# geigera-mullera.net
KiCad netlist of a schematic drawn in EAGLE
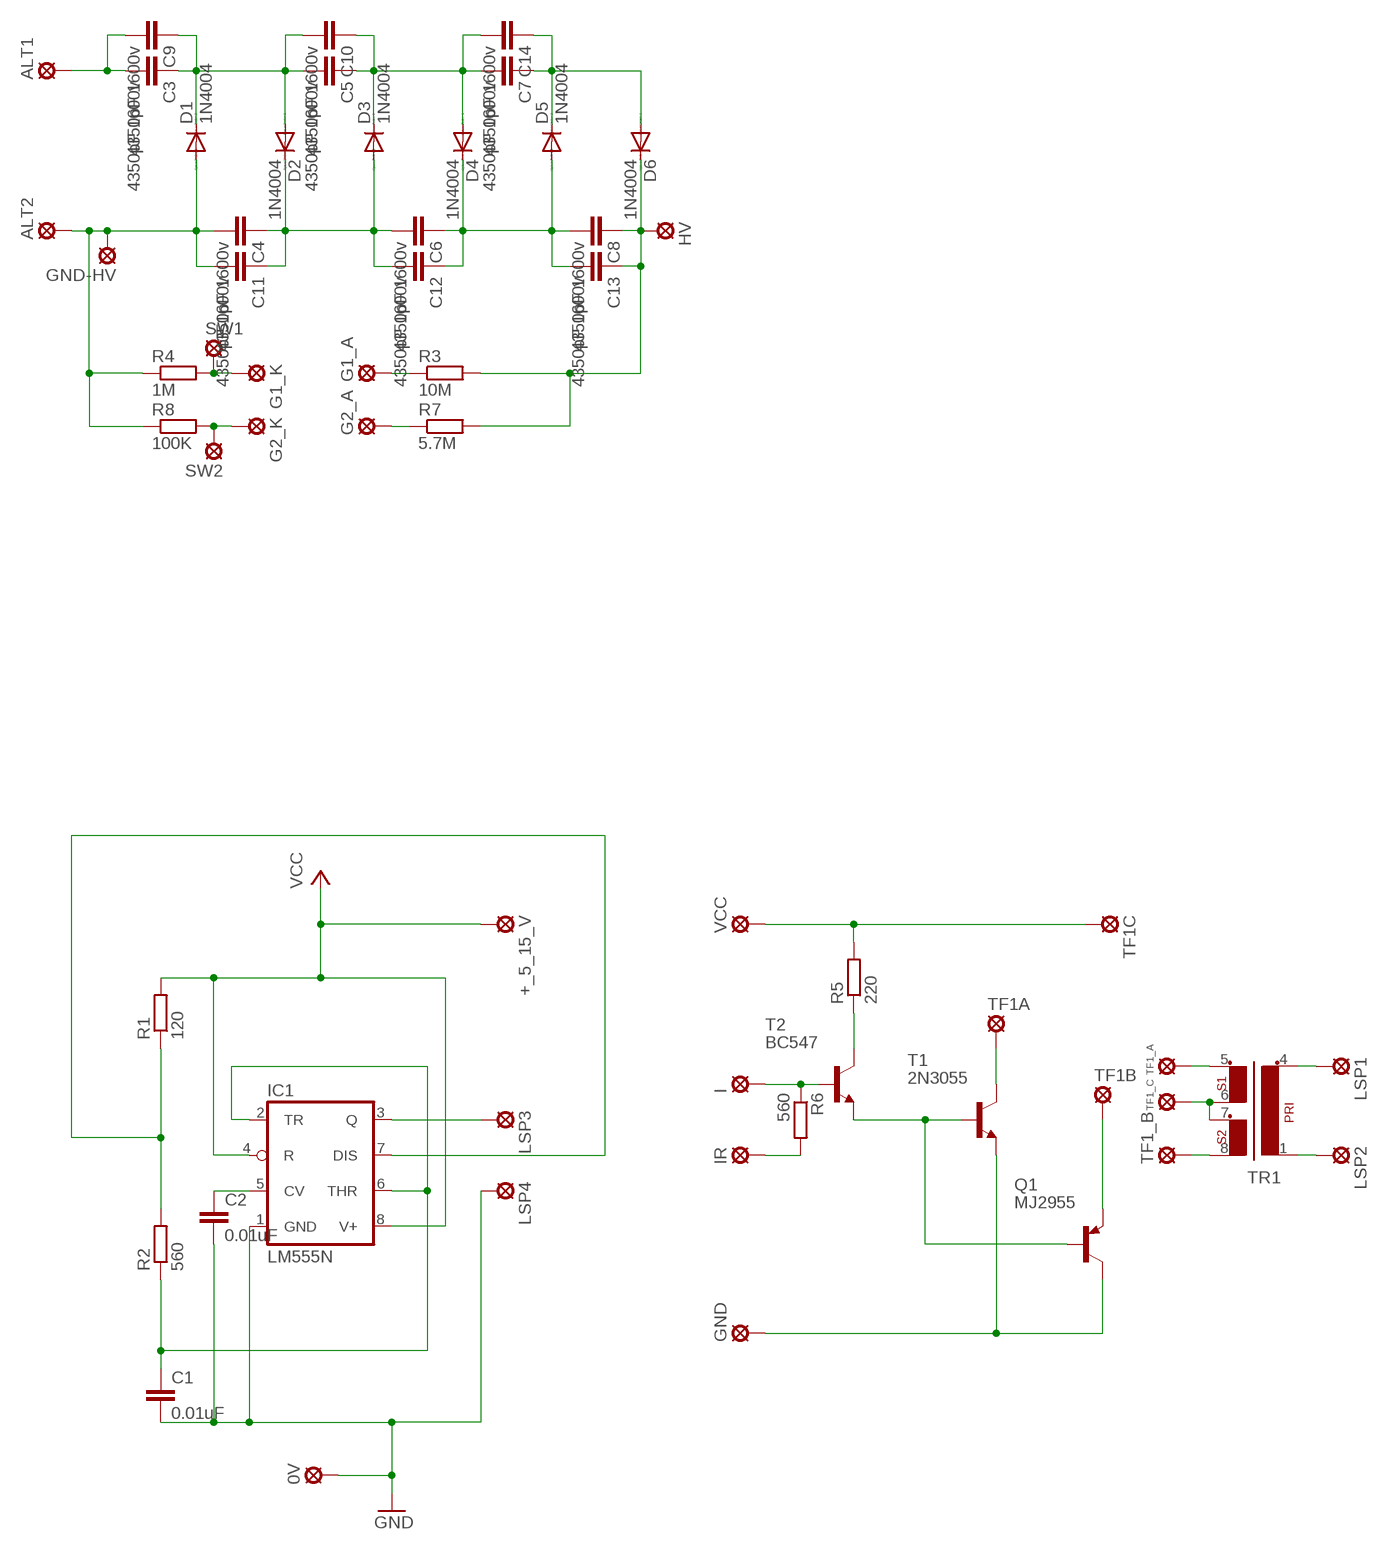
[diagram p0: schematic, sheet 1]

(export (version "E")
  (design (tool "Eeschema 10.0.6"))
  (components
    (comp (ref "+_5_15_V")
      (value "LSP10")
      (footprint "eagle-import:LSP10")
      (libsource (lib "eagle-import") (part "LSP10"))
    )
    (comp (ref "0V")
      (value "LSP10")
      (footprint "eagle-import:LSP10")
      (libsource (lib "eagle-import") (part "LSP10"))
    )
    (comp (ref "ALT1")
      (value "LSP10")
      (footprint "eagle-import:LSP10")
      (libsource (lib "eagle-import") (part "LSP10"))
    )
    (comp (ref "ALT2")
      (value "LSP10")
      (footprint "eagle-import:LSP10")
      (libsource (lib "eagle-import") (part "LSP10"))
    )
    (comp (ref "C1")
      (value "0.01uF")
      (footprint "eagle-import:C050-024X044")
      (libsource (lib "eagle-import") (part "resistor_C-EU050-024X044"))
    )
    (comp (ref "C2")
      (value "0.01uF")
      (footprint "eagle-import:C050-024X044")
      (libsource (lib "eagle-import") (part "resistor_C-EU050-024X044"))
    )
    (comp (ref "C3")
      (value "4350pF 1600v")
      (footprint "eagle-import:C225-074X268")
      (libsource (lib "eagle-import") (part "C-EU225-074X268"))
    )
    (comp (ref "C4")
      (value "4350pF 1600v")
      (footprint "eagle-import:C225-074X268")
      (libsource (lib "eagle-import") (part "C-EU225-074X268"))
    )
    (comp (ref "C5")
      (value "4350pF 1600v")
      (footprint "eagle-import:C225-074X268")
      (libsource (lib "eagle-import") (part "C-EU225-074X268"))
    )
    (comp (ref "C6")
      (value "4350pF 1600v")
      (footprint "eagle-import:C225-074X268")
      (libsource (lib "eagle-import") (part "C-EU225-074X268"))
    )
    (comp (ref "C7")
      (value "4350pF 1600v")
      (footprint "eagle-import:C225-074X268")
      (libsource (lib "eagle-import") (part "C-EU225-074X268"))
    )
    (comp (ref "C8")
      (value "4350pF 1600v")
      (footprint "eagle-import:C225-074X268")
      (libsource (lib "eagle-import") (part "C-EU225-074X268"))
    )
    (comp (ref "C9")
      (value "4350pF 1600v")
      (footprint "eagle-import:C225-074X268")
      (libsource (lib "eagle-import") (part "C-EU225-074X268"))
    )
    (comp (ref "C10")
      (value "4350pF 1600v")
      (footprint "eagle-import:C225-074X268")
      (libsource (lib "eagle-import") (part "C-EU225-074X268"))
    )
    (comp (ref "C11")
      (value "4350pF 1600v")
      (footprint "eagle-import:C225-074X268")
      (libsource (lib "eagle-import") (part "C-EU225-074X268"))
    )
    (comp (ref "C12")
      (value "4350pF 1600v")
      (footprint "eagle-import:C225-074X268")
      (libsource (lib "eagle-import") (part "C-EU225-074X268"))
    )
    (comp (ref "C13")
      (value "4350pF 1600v")
      (footprint "eagle-import:C225-074X268")
      (libsource (lib "eagle-import") (part "C-EU225-074X268"))
    )
    (comp (ref "C14")
      (value "4350pF 1600v")
      (footprint "eagle-import:C225-074X268")
      (libsource (lib "eagle-import") (part "C-EU225-074X268"))
    )
    (comp (ref "D1")
      (value "1N4004")
      (footprint "eagle-import:DO41-10")
      (libsource (lib "eagle-import") (part "1N4004"))
    )
    (comp (ref "D2")
      (value "1N4004")
      (footprint "eagle-import:DO41-10")
      (libsource (lib "eagle-import") (part "1N4004"))
    )
    (comp (ref "D3")
      (value "1N4004")
      (footprint "eagle-import:DO41-10")
      (libsource (lib "eagle-import") (part "1N4004"))
    )
    (comp (ref "D4")
      (value "1N4004")
      (footprint "eagle-import:DO41-10")
      (libsource (lib "eagle-import") (part "1N4004"))
    )
    (comp (ref "D5")
      (value "1N4004")
      (footprint "eagle-import:DO41-10")
      (libsource (lib "eagle-import") (part "1N4004"))
    )
    (comp (ref "D6")
      (value "1N4004")
      (footprint "eagle-import:DO41-10")
      (libsource (lib "eagle-import") (part "1N4004"))
    )
    (comp (ref "G1_A")
      (value "LSP10")
      (footprint "eagle-import:LSP10")
      (libsource (lib "eagle-import") (part "LSP10"))
    )
    (comp (ref "G1_K")
      (value "LSP10")
      (footprint "eagle-import:LSP10")
      (libsource (lib "eagle-import") (part "LSP10"))
    )
    (comp (ref "G2_A")
      (value "LSP10")
      (footprint "eagle-import:LSP10")
      (libsource (lib "eagle-import") (part "LSP10"))
    )
    (comp (ref "G2_K")
      (value "LSP10")
      (footprint "eagle-import:LSP10")
      (libsource (lib "eagle-import") (part "LSP10"))
    )
    (comp (ref "GND")
      (value "LSP10")
      (footprint "eagle-import:LSP10")
      (libsource (lib "eagle-import") (part "LSP10"))
    )
    (comp (ref "GND-HV")
      (value "LSP10")
      (footprint "eagle-import:LSP10")
      (libsource (lib "eagle-import") (part "LSP10"))
    )
    (comp (ref "HV")
      (value "LSP10")
      (footprint "eagle-import:LSP10")
      (libsource (lib "eagle-import") (part "LSP10"))
    )
    (comp (ref "I")
      (value "LSP10")
      (footprint "eagle-import:LSP10")
      (libsource (lib "eagle-import") (part "LSP10"))
    )
    (comp (ref "IC1")
      (value "LM555N")
      (footprint "eagle-import:DIL08-ROUND")
      (libsource (lib "eagle-import") (part "555NLM"))
    )
    (comp (ref "IR")
      (value "LSP10")
      (footprint "eagle-import:LSP10")
      (libsource (lib "eagle-import") (part "LSP10"))
    )
    (comp (ref "LSP1")
      (value "LSP10")
      (footprint "eagle-import:LSP10")
      (libsource (lib "eagle-import") (part "LSP10"))
    )
    (comp (ref "LSP2")
      (value "LSP10")
      (footprint "eagle-import:LSP10")
      (libsource (lib "eagle-import") (part "LSP10"))
    )
    (comp (ref "LSP3")
      (value "LSP10")
      (footprint "eagle-import:LSP10")
      (libsource (lib "eagle-import") (part "LSP10"))
    )
    (comp (ref "LSP4")
      (value "LSP10")
      (footprint "eagle-import:LSP10")
      (libsource (lib "eagle-import") (part "LSP10"))
    )
    (comp (ref "Q1")
      (value "MJ2955")
      (footprint "eagle-import:TO3")
      (libsource (lib "eagle-import") (part "MJ2955"))
    )
    (comp (ref "R1")
      (value "120")
      (footprint "eagle-import:0204_7")
      (libsource (lib "eagle-import") (part "resistor_R-EU_0204/7"))
    )
    (comp (ref "R2")
      (value "560")
      (footprint "eagle-import:0204_7")
      (libsource (lib "eagle-import") (part "resistor_R-EU_0204/7"))
    )
    (comp (ref "R3")
      (value "10M")
      (footprint "eagle-import:0207_10")
      (libsource (lib "eagle-import") (part "R-EU_0207/10"))
    )
    (comp (ref "R4")
      (value "1M")
      (footprint "eagle-import:0207_10")
      (libsource (lib "eagle-import") (part "R-EU_0207/10"))
    )
    (comp (ref "R5")
      (value "220")
      (footprint "eagle-import:0207_10")
      (libsource (lib "eagle-import") (part "R-EU_0207/10"))
    )
    (comp (ref "R6")
      (value "560")
      (footprint "eagle-import:0207_10")
      (libsource (lib "eagle-import") (part "R-EU_0207/10"))
    )
    (comp (ref "R7")
      (value "5.7M")
      (footprint "eagle-import:0207_10")
      (libsource (lib "eagle-import") (part "R-EU_0207/10"))
    )
    (comp (ref "R8")
      (value "100K")
      (footprint "eagle-import:0207_10")
      (libsource (lib "eagle-import") (part "R-EU_0207/10"))
    )
    (comp (ref "SW1")
      (value "LSP10")
      (footprint "eagle-import:LSP10")
      (libsource (lib "eagle-import") (part "LSP10"))
    )
    (comp (ref "SW2")
      (value "LSP10")
      (footprint "eagle-import:LSP10")
      (libsource (lib "eagle-import") (part "LSP10"))
    )
    (comp (ref "T1")
      (value "2N3055")
      (footprint "eagle-import:TO3")
      (libsource (lib "eagle-import") (part "2N3055"))
    )
    (comp (ref "T2")
      (value "BC547")
      (footprint "eagle-import:TO92")
      (libsource (lib "eagle-import") (part "BC547"))
    )
    (comp (ref "TF1A")
      (value "LSP10")
      (footprint "eagle-import:LSP10")
      (libsource (lib "eagle-import") (part "LSP10"))
    )
    (comp (ref "TF1B")
      (value "LSP10")
      (footprint "eagle-import:LSP10")
      (libsource (lib "eagle-import") (part "LSP10"))
    )
    (comp (ref "TF1C")
      (value "LSP10")
      (footprint "eagle-import:LSP10")
      (libsource (lib "eagle-import") (part "LSP10"))
    )
    (comp (ref "TF1_A")
      (value "LSP10")
      (footprint "eagle-import:LSP10")
      (libsource (lib "eagle-import") (part "LSP10"))
    )
    (comp (ref "TF1_B")
      (value "LSP10")
      (footprint "eagle-import:LSP10")
      (libsource (lib "eagle-import") (part "LSP10"))
    )
    (comp (ref "TF1_C")
      (value "LSP10")
      (footprint "eagle-import:LSP10")
      (libsource (lib "eagle-import") (part "LSP10"))
    )
    (comp (ref "TR1")
      (value "EE20-2")
      (footprint "eagle-import:EE20-2")
      (libsource (lib "eagle-import") (part "EE20-2"))
    )
    (comp (ref "VCC")
      (value "LSP10")
      (footprint "eagle-import:LSP10")
      (libsource (lib "eagle-import") (part "LSP10"))
    )
  )
  (nets
    (net (code "1") (name "GND") (class "Default")
      (node (ref "0V") (pin "MP") (pinfunction "MP_MP") (pintype "passive"))
      (node (ref "C1") (pin "2") (pinfunction "2_2") (pintype "passive"))
      (node (ref "C2") (pin "2") (pinfunction "2_2") (pintype "passive"))
      (node (ref "IC1") (pin "1") (pinfunction "GND_1") (pintype "power_in"))
      (node (ref "LSP4") (pin "MP") (pinfunction "MP_MP") (pintype "passive"))
    )
    (net (code "2") (name "Net-(ALT1-PadMP)") (class "Default")
      (node (ref "ALT1") (pin "MP") (pinfunction "MP_MP") (pintype "passive"))
      (node (ref "C3") (pin "2") (pinfunction "2_2") (pintype "passive"))
      (node (ref "C9") (pin "2") (pinfunction "2_2") (pintype "passive"))
    )
    (net (code "3") (name "Net-(ALT2-PadMP)") (class "Default")
      (node (ref "ALT2") (pin "MP") (pinfunction "MP_MP") (pintype "passive"))
      (node (ref "C11") (pin "2") (pinfunction "2_2") (pintype "passive"))
      (node (ref "C4") (pin "2") (pinfunction "2_2") (pintype "passive"))
      (node (ref "D1") (pin "A") (pinfunction "A_A") (pintype "passive"))
      (node (ref "GND-HV") (pin "MP") (pinfunction "MP_MP") (pintype "passive"))
      (node (ref "R4") (pin "1") (pinfunction "1_1") (pintype "passive"))
      (node (ref "R8") (pin "1") (pinfunction "1_1") (pintype "passive"))
    )
    (net (code "4") (name "Net-(C10-Pad1)") (class "Default")
      (node (ref "C10") (pin "1") (pinfunction "1_1") (pintype "passive"))
      (node (ref "C14") (pin "2") (pinfunction "2_2") (pintype "passive"))
      (node (ref "C5") (pin "1") (pinfunction "1_1") (pintype "passive"))
      (node (ref "C7") (pin "2") (pinfunction "2_2") (pintype "passive"))
      (node (ref "D3") (pin "C") (pinfunction "C_C") (pintype "passive"))
      (node (ref "D4") (pin "A") (pinfunction "A_A") (pintype "passive"))
    )
    (net (code "5") (name "Net-(C10-Pad2)") (class "Default")
      (node (ref "C10") (pin "2") (pinfunction "2_2") (pintype "passive"))
      (node (ref "C3") (pin "1") (pinfunction "1_1") (pintype "passive"))
      (node (ref "C5") (pin "2") (pinfunction "2_2") (pintype "passive"))
      (node (ref "C9") (pin "1") (pinfunction "1_1") (pintype "passive"))
      (node (ref "D1") (pin "C") (pinfunction "C_C") (pintype "passive"))
      (node (ref "D2") (pin "A") (pinfunction "A_A") (pintype "passive"))
    )
    (net (code "6") (name "Net-(C11-Pad1)") (class "Default")
      (node (ref "C11") (pin "1") (pinfunction "1_1") (pintype "passive"))
      (node (ref "C12") (pin "2") (pinfunction "2_2") (pintype "passive"))
      (node (ref "C4") (pin "1") (pinfunction "1_1") (pintype "passive"))
      (node (ref "C6") (pin "2") (pinfunction "2_2") (pintype "passive"))
      (node (ref "D2") (pin "C") (pinfunction "C_C") (pintype "passive"))
      (node (ref "D3") (pin "A") (pinfunction "A_A") (pintype "passive"))
    )
    (net (code "7") (name "Net-(C12-Pad1)") (class "Default")
      (node (ref "C12") (pin "1") (pinfunction "1_1") (pintype "passive"))
      (node (ref "C13") (pin "2") (pinfunction "2_2") (pintype "passive"))
      (node (ref "C6") (pin "1") (pinfunction "1_1") (pintype "passive"))
      (node (ref "C8") (pin "2") (pinfunction "2_2") (pintype "passive"))
      (node (ref "D4") (pin "C") (pinfunction "C_C") (pintype "passive"))
      (node (ref "D5") (pin "A") (pinfunction "A_A") (pintype "passive"))
    )
    (net (code "8") (name "Net-(C13-Pad1)") (class "Default")
      (node (ref "C13") (pin "1") (pinfunction "1_1") (pintype "passive"))
      (node (ref "C8") (pin "1") (pinfunction "1_1") (pintype "passive"))
      (node (ref "D6") (pin "C") (pinfunction "C_C") (pintype "passive"))
      (node (ref "HV") (pin "MP") (pinfunction "MP_MP") (pintype "passive"))
      (node (ref "R3") (pin "2") (pinfunction "2_2") (pintype "passive"))
      (node (ref "R7") (pin "2") (pinfunction "2_2") (pintype "passive"))
    )
    (net (code "9") (name "Net-(C14-Pad1)") (class "Default")
      (node (ref "C14") (pin "1") (pinfunction "1_1") (pintype "passive"))
      (node (ref "C7") (pin "1") (pinfunction "1_1") (pintype "passive"))
      (node (ref "D5") (pin "C") (pinfunction "C_C") (pintype "passive"))
      (node (ref "D6") (pin "A") (pinfunction "A_A") (pintype "passive"))
    )
    (net (code "10") (name "Net-(G1_A-PadMP)") (class "Default")
      (node (ref "G1_A") (pin "MP") (pinfunction "MP_MP") (pintype "passive"))
      (node (ref "R3") (pin "1") (pinfunction "1_1") (pintype "passive"))
    )
    (net (code "11") (name "Net-(G1_K-PadMP)") (class "Default")
      (node (ref "G1_K") (pin "MP") (pinfunction "MP_MP") (pintype "passive"))
      (node (ref "R4") (pin "2") (pinfunction "2_2") (pintype "passive"))
      (node (ref "SW1") (pin "MP") (pinfunction "MP_MP") (pintype "passive"))
    )
    (net (code "12") (name "Net-(G2_A-PadMP)") (class "Default")
      (node (ref "G2_A") (pin "MP") (pinfunction "MP_MP") (pintype "passive"))
      (node (ref "R7") (pin "1") (pinfunction "1_1") (pintype "passive"))
    )
    (net (code "13") (name "Net-(G2_K-PadMP)") (class "Default")
      (node (ref "G2_K") (pin "MP") (pinfunction "MP_MP") (pintype "passive"))
      (node (ref "R8") (pin "2") (pinfunction "2_2") (pintype "passive"))
      (node (ref "SW2") (pin "MP") (pinfunction "MP_MP") (pintype "passive"))
    )
    (net (code "14") (name "Net-(GND-PadMP)") (class "Default")
      (node (ref "GND") (pin "MP") (pinfunction "MP_MP") (pintype "passive"))
      (node (ref "Q1") (pin "C") (pinfunction "C_C") (pintype "passive"))
      (node (ref "Q1") (pin "C/") (pinfunction "C_C/") (pintype "passive"))
      (node (ref "T1") (pin "E") (pinfunction "E_E") (pintype "passive"))
    )
    (net (code "15") (name "Net-(IC1-CV)") (class "Default")
      (node (ref "C2") (pin "1") (pinfunction "1_1") (pintype "passive"))
      (node (ref "IC1") (pin "5") (pinfunction "CV_5") (pintype "input"))
    )
    (net (code "16") (name "Net-(IC1-DIS)") (class "Default")
      (node (ref "IC1") (pin "7") (pinfunction "DIS_7") (pintype "input"))
      (node (ref "R1") (pin "1") (pinfunction "1_1") (pintype "passive"))
      (node (ref "R2") (pin "2") (pinfunction "2_2") (pintype "passive"))
    )
    (net (code "17") (name "Net-(IC1-Q)") (class "Default")
      (node (ref "IC1") (pin "3") (pinfunction "Q_3") (pintype "output"))
      (node (ref "LSP3") (pin "MP") (pinfunction "MP_MP") (pintype "passive"))
    )
    (net (code "18") (name "Net-(IC1-THR)") (class "Default")
      (node (ref "C1") (pin "1") (pinfunction "1_1") (pintype "passive"))
      (node (ref "IC1") (pin "2") (pinfunction "TR_2") (pintype "input"))
      (node (ref "IC1") (pin "6") (pinfunction "THR_6") (pintype "input"))
      (node (ref "R2") (pin "1") (pinfunction "1_1") (pintype "passive"))
    )
    (net (code "19") (name "Net-(IR-PadMP)") (class "Default")
      (node (ref "IR") (pin "MP") (pinfunction "MP_MP") (pintype "passive"))
      (node (ref "R6") (pin "2") (pinfunction "2_2") (pintype "passive"))
    )
    (net (code "20") (name "Net-(LSP2-PadMP)") (class "Default")
      (node (ref "LSP2") (pin "MP") (pinfunction "MP_MP") (pintype "passive"))
      (node (ref "TR1") (pin "1") (pinfunction "1_1") (pintype "passive"))
    )
    (net (code "21") (name "Net-(Q1-PadE)") (class "Default")
      (node (ref "Q1") (pin "E") (pinfunction "E_E") (pintype "passive"))
      (node (ref "TF1B") (pin "MP") (pinfunction "MP_MP") (pintype "passive"))
    )
    (net (code "22") (name "Net-(R5-Pad2)") (class "Default")
      (node (ref "R5") (pin "2") (pinfunction "2_2") (pintype "passive"))
      (node (ref "TF1C") (pin "MP") (pinfunction "MP_MP") (pintype "passive"))
      (node (ref "VCC") (pin "MP") (pinfunction "MP_MP") (pintype "passive"))
    )
    (net (code "23") (name "Net-(T1-C-PadC{slash})") (class "Default")
      (node (ref "T1") (pin "C") (pinfunction "C_C") (pintype "passive"))
      (node (ref "T1") (pin "C/") (pinfunction "C_C/") (pintype "passive"))
      (node (ref "TF1A") (pin "MP") (pinfunction "MP_MP") (pintype "passive"))
    )
    (net (code "24") (name "Net-(T2-B)") (class "Default")
      (node (ref "I") (pin "MP") (pinfunction "MP_MP") (pintype "passive"))
      (node (ref "R6") (pin "1") (pinfunction "1_1") (pintype "passive"))
      (node (ref "T2") (pin "2") (pinfunction "B_2") (pintype "passive"))
    )
    (net (code "25") (name "Net-(T2-C)") (class "Default")
      (node (ref "R5") (pin "1") (pinfunction "1_1") (pintype "passive"))
      (node (ref "T2") (pin "3") (pinfunction "C_3") (pintype "passive"))
    )
    (net (code "26") (name "Net-(T2-E)") (class "Default")
      (node (ref "Q1") (pin "B") (pinfunction "B_B") (pintype "passive"))
      (node (ref "T1") (pin "B") (pinfunction "B_B") (pintype "passive"))
      (node (ref "T2") (pin "1") (pinfunction "E_1") (pintype "passive"))
    )
    (net (code "27") (name "Net-(TR1-2)") (class "Default")
      (node (ref "LSP1") (pin "MP") (pinfunction "MP_MP") (pintype "passive"))
      (node (ref "TR1") (pin "4") (pinfunction "2_4") (pintype "passive"))
    )
    (net (code "28") (name "Net-(TR1-3)") (class "Default")
      (node (ref "TF1_A") (pin "MP") (pinfunction "MP_MP") (pintype "passive"))
      (node (ref "TR1") (pin "5") (pinfunction "3_5") (pintype "passive"))
    )
    (net (code "29") (name "Net-(TR1-4)") (class "Default")
      (node (ref "TF1_C") (pin "MP") (pinfunction "MP_MP") (pintype "passive"))
      (node (ref "TR1") (pin "6") (pinfunction "4_6") (pintype "passive"))
      (node (ref "TR1") (pin "7") (pinfunction "5_7") (pintype "passive"))
    )
    (net (code "30") (name "Net-(TR1-6)") (class "Default")
      (node (ref "TF1_B") (pin "MP") (pinfunction "MP_MP") (pintype "passive"))
      (node (ref "TR1") (pin "8") (pinfunction "6_8") (pintype "passive"))
    )
    (net (code "31") (name "VCC") (class "Default")
      (node (ref "+_5_15_V") (pin "MP") (pinfunction "MP_MP") (pintype "passive"))
      (node (ref "IC1") (pin "4") (pinfunction "R_4") (pintype "input"))
      (node (ref "IC1") (pin "8") (pinfunction "V+_8") (pintype "power_in"))
      (node (ref "R1") (pin "2") (pinfunction "2_2") (pintype "passive"))
    )
  )
)
